# Smart_AC_Meter.net
KiCad netlist of a schematic drawn in Altium Designer
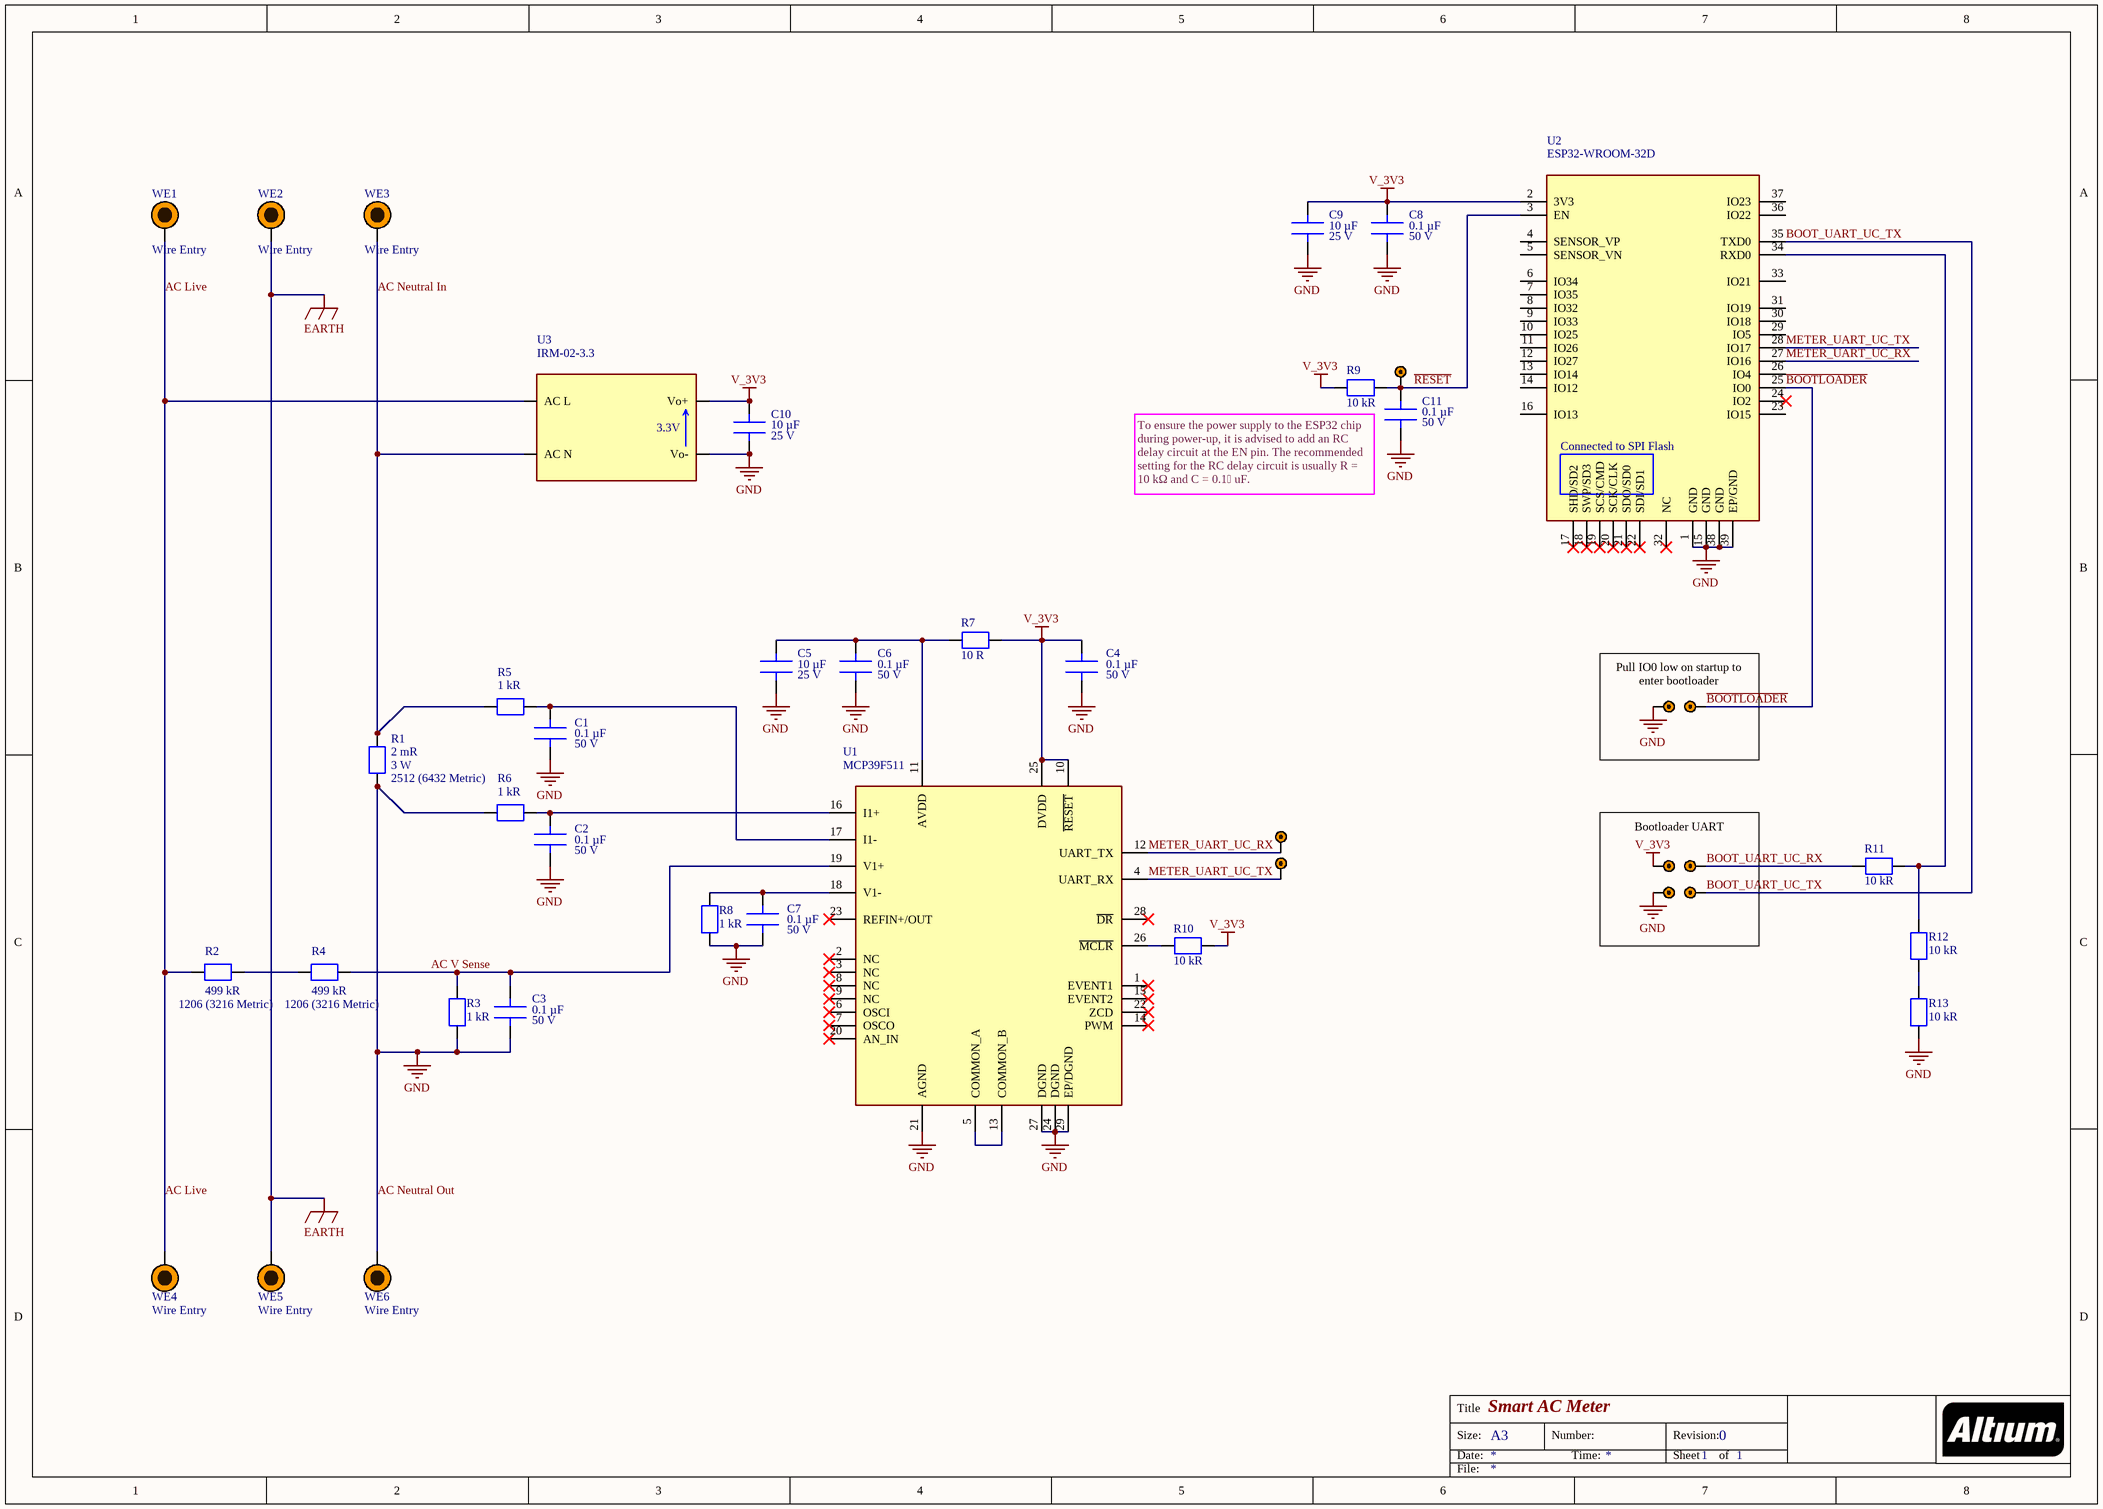
[diagram p0: Smart_AC_Meter.SchDoc]

(export (version "E")
  (design (tool "Eeschema 10.0.6"))
  (components
    (comp (ref "C1")
      (value "Capacitor")
      (footprint "0805")
      (description "AVX Corporation 08055D104KAT2A")
      (fields
        (field (name "UNIQUE PART NUMBER") "LM_CAP_0001")
        (field (name "DIGIKEY PART NUMBER") "478-12790-1-ND")
        (field (name "CAPACITANCE") "0.1 µF")
        (field (name "VOLTAGE") "50 V")
      )
      (libsource (lib "Database") (part "Capacitor"))
    )
    (comp (ref "C2")
      (value "Capacitor")
      (footprint "0805")
      (description "AVX Corporation 08055D104KAT2A")
      (fields
        (field (name "UNIQUE PART NUMBER") "LM_CAP_0001")
        (field (name "DIGIKEY PART NUMBER") "478-12790-1-ND")
        (field (name "CAPACITANCE") "0.1 µF")
        (field (name "VOLTAGE") "50 V")
      )
      (libsource (lib "Database") (part "Capacitor"))
    )
    (comp (ref "C3")
      (value "Capacitor")
      (footprint "0805")
      (description "AVX Corporation 08055D104KAT2A")
      (fields
        (field (name "CAPACITANCE") "0.1 µF")
        (field (name "UNIQUE PART NUMBER") "LM_CAP_0001")
        (field (name "DIGIKEY PART NUMBER") "478-12790-1-ND")
        (field (name "VOLTAGE") "50 V")
      )
      (libsource (lib "Database") (part "Capacitor"))
    )
    (comp (ref "C4")
      (value "Capacitor")
      (footprint "0805")
      (description "AVX Corporation 08055D104KAT2A")
      (fields
        (field (name "UNIQUE PART NUMBER") "LM_CAP_0001")
        (field (name "DIGIKEY PART NUMBER") "478-12790-1-ND")
        (field (name "CAPACITANCE") "0.1 µF")
        (field (name "VOLTAGE") "50 V")
      )
      (libsource (lib "Database") (part "Capacitor"))
    )
    (comp (ref "C5")
      (value "Capacitor")
      (footprint "0805")
      (fields
        (field (name "CAPACITANCE") "10 µF")
        (field (name "UNIQUE PART NUMBER") "LM_CAP_0002")
        (field (name "MANUFACTURER PART NUMBER") "Taiyo Yuden TMK212BBJ106KG-T")
        (field (name "DIGIKEY PART NUMBER") "587-2985-1-ND")
        (field (name "VOLTAGE") "25 V")
      )
      (libsource (lib "Database") (part "Capacitor"))
    )
    (comp (ref "C6")
      (value "Capacitor")
      (footprint "0805")
      (description "AVX Corporation 08055D104KAT2A")
      (fields
        (field (name "UNIQUE PART NUMBER") "LM_CAP_0001")
        (field (name "DIGIKEY PART NUMBER") "478-12790-1-ND")
        (field (name "CAPACITANCE") "0.1 µF")
        (field (name "VOLTAGE") "50 V")
      )
      (libsource (lib "Database") (part "Capacitor"))
    )
    (comp (ref "C7")
      (value "Capacitor")
      (footprint "0805")
      (description "AVX Corporation 08055D104KAT2A")
      (fields
        (field (name "CAPACITANCE") "0.1 µF")
        (field (name "UNIQUE PART NUMBER") "LM_CAP_0001")
        (field (name "DIGIKEY PART NUMBER") "478-12790-1-ND")
        (field (name "VOLTAGE") "50 V")
      )
      (libsource (lib "Database") (part "Capacitor"))
    )
    (comp (ref "C8")
      (value "Capacitor")
      (footprint "0805")
      (description "AVX Corporation 08055D104KAT2A")
      (fields
        (field (name "UNIQUE PART NUMBER") "LM_CAP_0001")
        (field (name "DIGIKEY PART NUMBER") "478-12790-1-ND")
        (field (name "CAPACITANCE") "0.1 µF")
        (field (name "VOLTAGE") "50 V")
      )
      (libsource (lib "Database") (part "Capacitor"))
    )
    (comp (ref "C9")
      (value "Capacitor")
      (footprint "0805")
      (fields
        (field (name "CAPACITANCE") "10 µF")
        (field (name "UNIQUE PART NUMBER") "LM_CAP_0002")
        (field (name "MANUFACTURER PART NUMBER") "Taiyo Yuden TMK212BBJ106KG-T")
        (field (name "DIGIKEY PART NUMBER") "587-2985-1-ND")
        (field (name "VOLTAGE") "25 V")
      )
      (libsource (lib "Database") (part "Capacitor"))
    )
    (comp (ref "C10")
      (value "Capacitor")
      (footprint "0805")
      (fields
        (field (name "CAPACITANCE") "10 µF")
        (field (name "UNIQUE PART NUMBER") "LM_CAP_0002")
        (field (name "MANUFACTURER PART NUMBER") "Taiyo Yuden TMK212BBJ106KG-T")
        (field (name "DIGIKEY PART NUMBER") "587-2985-1-ND")
        (field (name "VOLTAGE") "25 V")
      )
      (libsource (lib "Database") (part "Capacitor"))
    )
    (comp (ref "C11")
      (value "Capacitor")
      (footprint "0805")
      (description "AVX Corporation 08055D104KAT2A")
      (fields
        (field (name "UNIQUE PART NUMBER") "LM_CAP_0001")
        (field (name "DIGIKEY PART NUMBER") "478-12790-1-ND")
        (field (name "CAPACITANCE") "0.1 µF")
        (field (name "VOLTAGE") "50 V")
      )
      (libsource (lib "Database") (part "Capacitor"))
    )
    (comp (ref "R1")
      (value "Resistor")
      (footprint "2512")
      (fields
        (field (name "UNIQUE PART NUMBER") "LM_RES_0002")
        (field (name "MANUFACTURER PART NUMBER") "Riedon CSRL3-0R002F8")
        (field (name "DIGIKEY PART NUMBER") "696-1836-1-ND")
        (field (name "RESISTANCE") "2 mR")
        (field (name "POWER") "3 W")
        (field (name "PACKAGE") "2512 (6432 Metric)")
      )
      (libsource (lib "Database") (part "Resistor"))
    )
    (comp (ref "R2")
      (value "Resistor")
      (footprint "1206")
      (fields
        (field (name "UNIQUE PART NUMBER") "LM_RES_0003")
        (field (name "MANUFACTURER PART NUMBER") "Stackpole Electronics Inc RMCF1206FT499K")
        (field (name "DIGIKEY PART NUMBER") "RMCF1206FT499KCT-ND")
        (field (name "RESISTANCE") "499 kR")
        (field (name "PACKAGE") "1206 (3216 Metric)")
      )
      (libsource (lib "Database") (part "Resistor"))
    )
    (comp (ref "R3")
      (value "Resistor")
      (footprint "0805")
      (fields
        (field (name "UNIQUE PART NUMBER") "LM_RES_0001")
        (field (name "MANUFACTURER PART NUMBER") "Stackpole Electronics Inc RMCF0805FT1K00")
        (field (name "DIGIKEY PART NUMBER") "RMCF0805FT1K00CT-ND")
        (field (name "RESISTANCE") "1 kR")
      )
      (libsource (lib "Database") (part "Resistor"))
    )
    (comp (ref "R4")
      (value "Resistor")
      (footprint "1206")
      (fields
        (field (name "UNIQUE PART NUMBER") "LM_RES_0003")
        (field (name "MANUFACTURER PART NUMBER") "Stackpole Electronics Inc RMCF1206FT499K")
        (field (name "DIGIKEY PART NUMBER") "RMCF1206FT499KCT-ND")
        (field (name "RESISTANCE") "499 kR")
        (field (name "PACKAGE") "1206 (3216 Metric)")
      )
      (libsource (lib "Database") (part "Resistor"))
    )
    (comp (ref "R5")
      (value "Resistor")
      (footprint "0805")
      (fields
        (field (name "UNIQUE PART NUMBER") "LM_RES_0001")
        (field (name "MANUFACTURER PART NUMBER") "Stackpole Electronics Inc RMCF0805FT1K00")
        (field (name "DIGIKEY PART NUMBER") "RMCF0805FT1K00CT-ND")
        (field (name "RESISTANCE") "1 kR")
      )
      (libsource (lib "Database") (part "Resistor"))
    )
    (comp (ref "R6")
      (value "Resistor")
      (footprint "0805")
      (fields
        (field (name "UNIQUE PART NUMBER") "LM_RES_0001")
        (field (name "MANUFACTURER PART NUMBER") "Stackpole Electronics Inc RMCF0805FT1K00")
        (field (name "DIGIKEY PART NUMBER") "RMCF0805FT1K00CT-ND")
        (field (name "RESISTANCE") "1 kR")
      )
      (libsource (lib "Database") (part "Resistor"))
    )
    (comp (ref "R7")
      (value "Resistor")
      (footprint "0805")
      (fields
        (field (name "RESISTANCE") "10 R")
        (field (name "UNIQUE PART NUMBER") "LM_RES_0004")
        (field (name "MANUFACTURER PART NUMBER") "Stackpole Electronics Inc RMCF0805FT10R0")
        (field (name "DIGIKEY PART NUMBER") "RMCF0805FT10R0CT-ND")
      )
      (libsource (lib "Database") (part "Resistor"))
    )
    (comp (ref "R8")
      (value "Resistor")
      (footprint "0805")
      (fields
        (field (name "UNIQUE PART NUMBER") "LM_RES_0001")
        (field (name "MANUFACTURER PART NUMBER") "Stackpole Electronics Inc RMCF0805FT1K00")
        (field (name "DIGIKEY PART NUMBER") "RMCF0805FT1K00CT-ND")
        (field (name "RESISTANCE") "1 kR")
      )
      (libsource (lib "Database") (part "Resistor"))
    )
    (comp (ref "R9")
      (value "Resistor")
      (footprint "0805")
      (fields
        (field (name "RESISTANCE") "10 kR")
        (field (name "UNIQUE PART NUMBER") "LM_RES_0005")
        (field (name "MANUFACTURER PART NUMBER") "Stackpole Electronics Inc RMCF0805FT10K0")
        (field (name "DIGIKEY PART NUMBER") "RMCF0805FT10K0CT-ND")
      )
      (libsource (lib "Database") (part "Resistor"))
    )
    (comp (ref "R10")
      (value "Resistor")
      (footprint "0805")
      (fields
        (field (name "RESISTANCE") "10 kR")
        (field (name "UNIQUE PART NUMBER") "LM_RES_0005")
        (field (name "MANUFACTURER PART NUMBER") "Stackpole Electronics Inc RMCF0805FT10K0")
        (field (name "DIGIKEY PART NUMBER") "RMCF0805FT10K0CT-ND")
      )
      (libsource (lib "Database") (part "Resistor"))
    )
    (comp (ref "R11")
      (value "Resistor")
      (footprint "0805")
      (fields
        (field (name "RESISTANCE") "10 kR")
        (field (name "UNIQUE PART NUMBER") "LM_RES_0005")
        (field (name "MANUFACTURER PART NUMBER") "Stackpole Electronics Inc RMCF0805FT10K0")
        (field (name "DIGIKEY PART NUMBER") "RMCF0805FT10K0CT-ND")
      )
      (libsource (lib "Database") (part "Resistor"))
    )
    (comp (ref "R12")
      (value "Resistor")
      (footprint "0805")
      (fields
        (field (name "RESISTANCE") "10 kR")
        (field (name "UNIQUE PART NUMBER") "LM_RES_0005")
        (field (name "MANUFACTURER PART NUMBER") "Stackpole Electronics Inc RMCF0805FT10K0")
        (field (name "DIGIKEY PART NUMBER") "RMCF0805FT10K0CT-ND")
      )
      (libsource (lib "Database") (part "Resistor"))
    )
    (comp (ref "R13")
      (value "Resistor")
      (footprint "0805")
      (fields
        (field (name "RESISTANCE") "10 kR")
        (field (name "UNIQUE PART NUMBER") "LM_RES_0005")
        (field (name "MANUFACTURER PART NUMBER") "Stackpole Electronics Inc RMCF0805FT10K0")
        (field (name "DIGIKEY PART NUMBER") "RMCF0805FT10K0CT-ND")
      )
      (libsource (lib "Database") (part "Resistor"))
    )
    (comp (ref "TP1")
      (value "Via")
      (footprint "1mmVia")
      (description "1mm dia via/through hole")
      (fields (field (name "UNIQUE PART NUMBER") "LM_OTH_0002"))
      (libsource (lib "Database") (part "Via"))
    )
    (comp (ref "TP2")
      (value "Via")
      (footprint "1mmVia")
      (description "1mm dia via/through hole")
      (fields (field (name "UNIQUE PART NUMBER") "LM_OTH_0002"))
      (libsource (lib "Database") (part "Via"))
    )
    (comp (ref "TP3")
      (value "Via")
      (footprint "1mmVia")
      (description "1mm dia via/through hole")
      (fields (field (name "UNIQUE PART NUMBER") "LM_OTH_0002"))
      (libsource (lib "Database") (part "Via"))
    )
    (comp (ref "TP4")
      (value "Via")
      (footprint "1mmVia")
      (description "1mm dia via/through hole")
      (fields (field (name "UNIQUE PART NUMBER") "LM_OTH_0002"))
      (libsource (lib "Database") (part "Via"))
    )
    (comp (ref "TP5")
      (value "Via")
      (footprint "1mmVia")
      (description "1mm dia via/through hole")
      (fields (field (name "UNIQUE PART NUMBER") "LM_OTH_0002"))
      (libsource (lib "Database") (part "Via"))
    )
    (comp (ref "TP6")
      (value "Via")
      (footprint "1mmVia")
      (description "1mm dia via/through hole")
      (fields (field (name "UNIQUE PART NUMBER") "LM_OTH_0002"))
      (libsource (lib "Database") (part "Via"))
    )
    (comp (ref "TP7")
      (value "Via")
      (footprint "1mmVia")
      (description "1mm dia via/through hole")
      (fields (field (name "UNIQUE PART NUMBER") "LM_OTH_0002"))
      (libsource (lib "Database") (part "Via"))
    )
    (comp (ref "TP8")
      (value "Via")
      (footprint "1mmVia")
      (description "1mm dia via/through hole")
      (fields (field (name "UNIQUE PART NUMBER") "LM_OTH_0002"))
      (libsource (lib "Database") (part "Via"))
    )
    (comp (ref "TP9")
      (value "Via")
      (footprint "1mmVia")
      (description "1mm dia via/through hole")
      (fields (field (name "UNIQUE PART NUMBER") "LM_OTH_0002"))
      (libsource (lib "Database") (part "Via"))
    )
    (comp (ref "U1")
      (value "MCP39F511")
      (footprint "MCP39F511")
      (description "Single Phase Meter IC 28-QFN (5x5)")
      (fields
        (field (name "UNIQUE PART NUMBER") "LM_IC_0001")
        (field (name "MANUFACTURER PART NUMBER") "Microchip Technology MCP39F511-E/MQ")
      )
      (libsource (lib "Database") (part "MCP39F511"))
    )
    (comp (ref "U2")
      (value "ESP32-WROOM-32D")
      (footprint "ESP32-WROOM-32D")
      (description "Bluetooth, WiFi,3 Transceiver Module")
      (fields
        (field (name "UNIQUE PART NUMBER") "LM_IC_0002")
        (field (name "MANUFACTURER PART NUMBER") "Espressif Systems ESP32-WROOM-32D")
      )
      (libsource (lib "Database") (part "ESP32-WROOM-32D"))
    )
    (comp (ref "U3")
      (value "IRM-02-3.3")
      (footprint "IRM-02-3.3")
      (description "Enclosed AC DC Converter 1 Output 3.3V 600mA")
      (fields
        (field (name "UNIQUE PART NUMBER") "LM_IC_0003")
        (field (name "MANUFACTURER PART NUMBER") "MEAN WELL USA Inc. IRM-02-3.3")
      )
      (libsource (lib "Database") (part "IRM-02-3.3"))
    )
    (comp (ref "WE1")
      (value "Wire Entry")
      (footprint "12AWGWireEntry")
      (description "12 AWG Wire Entry")
      (fields (field (name "UNIQUE PART NUMBER") "LM_OTH_0001"))
      (libsource (lib "Database") (part "Wire Entry"))
    )
    (comp (ref "WE2")
      (value "Wire Entry")
      (footprint "12AWGWireEntry")
      (description "12 AWG Wire Entry")
      (fields (field (name "UNIQUE PART NUMBER") "LM_OTH_0001"))
      (libsource (lib "Database") (part "Wire Entry"))
    )
    (comp (ref "WE3")
      (value "Wire Entry")
      (footprint "12AWGWireEntry")
      (description "12 AWG Wire Entry")
      (fields (field (name "UNIQUE PART NUMBER") "LM_OTH_0001"))
      (libsource (lib "Database") (part "Wire Entry"))
    )
    (comp (ref "WE4")
      (value "Wire Entry")
      (footprint "12AWGWireEntry")
      (description "12 AWG Wire Entry")
      (fields (field (name "UNIQUE PART NUMBER") "LM_OTH_0001"))
      (libsource (lib "Database") (part "Wire Entry"))
    )
    (comp (ref "WE5")
      (value "Wire Entry")
      (footprint "12AWGWireEntry")
      (description "12 AWG Wire Entry")
      (fields (field (name "UNIQUE PART NUMBER") "LM_OTH_0001"))
      (libsource (lib "Database") (part "Wire Entry"))
    )
    (comp (ref "WE6")
      (value "Wire Entry")
      (footprint "12AWGWireEntry")
      (description "12 AWG Wire Entry")
      (fields (field (name "UNIQUE PART NUMBER") "LM_OTH_0001"))
      (libsource (lib "Database") (part "Wire Entry"))
    )
  )
  (nets
    (net (code "1") (name "/AC Live") (class "Default")
      (node (ref "R2") (pin "1") (pinfunction "1_1") (pintype "passive"))
      (node (ref "U3") (pin "1") (pinfunction "AC_L_1") (pintype "passive"))
      (node (ref "WE1") (pin "1") (pinfunction "1_1") (pintype "passive"))
      (node (ref "WE4") (pin "1") (pinfunction "1_1") (pintype "passive"))
    )
    (net (code "2") (name "/AC Neutral In") (class "Default")
      (node (ref "R1") (pin "1") (pinfunction "1_1") (pintype "passive"))
      (node (ref "R5") (pin "1") (pinfunction "1_1") (pintype "passive"))
      (node (ref "U3") (pin "24") (pinfunction "AC_N_24") (pintype "passive"))
      (node (ref "WE3") (pin "1") (pinfunction "1_1") (pintype "passive"))
    )
    (net (code "3") (name "/AC V Sense") (class "Default")
      (node (ref "C3") (pin "1") (pinfunction "1_1") (pintype "passive"))
      (node (ref "R3") (pin "1") (pinfunction "1_1") (pintype "passive"))
      (node (ref "R4") (pin "2") (pinfunction "2_2") (pintype "passive"))
      (node (ref "U1") (pin "19") (pinfunction "V1+_19") (pintype "passive"))
    )
    (net (code "4") (name "/BOOT_UART_UC_RX") (class "Default")
      (node (ref "R11") (pin "1") (pinfunction "1_1") (pintype "passive"))
      (node (ref "TP4") (pin "1") (pinfunction "1_1") (pintype "passive"))
    )
    (net (code "5") (name "/BOOT_UART_UC_TX") (class "Default")
      (node (ref "TP6") (pin "1") (pinfunction "1_1") (pintype "passive"))
      (node (ref "U2") (pin "35") (pinfunction "TXD0_35") (pintype "passive"))
    )
    (net (code "6") (name "/METER_UART_UC_RX") (class "Default")
      (node (ref "TP7") (pin "1") (pinfunction "1_1") (pintype "passive"))
      (node (ref "U1") (pin "12") (pinfunction "UART_TX_12") (pintype "passive"))
      (node (ref "U2") (pin "27") (pinfunction "IO16_27") (pintype "passive"))
    )
    (net (code "7") (name "/METER_UART_UC_TX") (class "Default")
      (node (ref "TP8") (pin "1") (pinfunction "1_1") (pintype "passive"))
      (node (ref "U1") (pin "4") (pinfunction "UART_RX_4") (pintype "passive"))
      (node (ref "U2") (pin "28") (pinfunction "IO17_28") (pintype "passive"))
    )
    (net (code "8") (name "/~{BOOTLOADER}") (class "Default")
      (node (ref "TP2") (pin "1") (pinfunction "1_1") (pintype "passive"))
      (node (ref "U2") (pin "25") (pinfunction "IO0_25") (pintype "passive"))
    )
    (net (code "9") (name "/~{RESET}") (class "Default")
      (node (ref "C11") (pin "1") (pinfunction "1_1") (pintype "passive"))
      (node (ref "R9") (pin "2") (pinfunction "2_2") (pintype "passive"))
      (node (ref "TP9") (pin "1") (pinfunction "1_1") (pintype "passive"))
      (node (ref "U2") (pin "3") (pinfunction "EN_3") (pintype "passive"))
    )
    (net (code "10") (name "EARTH") (class "Default")
      (node (ref "WE2") (pin "1") (pinfunction "1_1") (pintype "passive"))
      (node (ref "WE5") (pin "1") (pinfunction "1_1") (pintype "passive"))
    )
    (net (code "11") (name "GND") (class "Default")
      (node (ref "C1") (pin "2") (pinfunction "2_2") (pintype "passive"))
      (node (ref "C10") (pin "1") (pinfunction "1_1") (pintype "passive"))
      (node (ref "C11") (pin "2") (pinfunction "2_2") (pintype "passive"))
      (node (ref "C2") (pin "2") (pinfunction "2_2") (pintype "passive"))
      (node (ref "C3") (pin "2") (pinfunction "2_2") (pintype "passive"))
      (node (ref "C4") (pin "2") (pinfunction "2_2") (pintype "passive"))
      (node (ref "C5") (pin "2") (pinfunction "2_2") (pintype "passive"))
      (node (ref "C6") (pin "2") (pinfunction "2_2") (pintype "passive"))
      (node (ref "C7") (pin "2") (pinfunction "2_2") (pintype "passive"))
      (node (ref "C8") (pin "2") (pinfunction "2_2") (pintype "passive"))
      (node (ref "C9") (pin "1") (pinfunction "1_1") (pintype "passive"))
      (node (ref "R1") (pin "2") (pinfunction "2_2") (pintype "passive"))
      (node (ref "R13") (pin "1") (pinfunction "1_1") (pintype "passive"))
      (node (ref "R3") (pin "2") (pinfunction "2_2") (pintype "passive"))
      (node (ref "R6") (pin "1") (pinfunction "1_1") (pintype "passive"))
      (node (ref "R8") (pin "1") (pinfunction "1_1") (pintype "passive"))
      (node (ref "TP1") (pin "1") (pinfunction "1_1") (pintype "passive"))
      (node (ref "TP5") (pin "1") (pinfunction "1_1") (pintype "passive"))
      (node (ref "U1") (pin "21") (pinfunction "AGND_21") (pintype "passive"))
      (node (ref "U1") (pin "24") (pinfunction "DGND_24") (pintype "passive"))
      (node (ref "U1") (pin "27") (pinfunction "DGND_27") (pintype "passive"))
      (node (ref "U1") (pin "29") (pinfunction "EP/DGND_29") (pintype "passive"))
      (node (ref "U2") (pin "1") (pinfunction "GND_1") (pintype "passive"))
      (node (ref "U2") (pin "15") (pinfunction "GND_15") (pintype "passive"))
      (node (ref "U2") (pin "38") (pinfunction "GND_38") (pintype "passive"))
      (node (ref "U2") (pin "39") (pinfunction "EP/GND_39") (pintype "passive"))
      (node (ref "U3") (pin "13") (pinfunction "Vo-_13") (pintype "passive"))
      (node (ref "WE6") (pin "1") (pinfunction "1_1") (pintype "passive"))
    )
    (net (code "12") (name "Net-(R2-Pad2)") (class "Default")
      (node (ref "R2") (pin "2") (pinfunction "2_2") (pintype "passive"))
      (node (ref "R4") (pin "1") (pinfunction "1_1") (pintype "passive"))
    )
    (net (code "13") (name "Net-(R12-Pad1)") (class "Default")
      (node (ref "R12") (pin "1") (pinfunction "1_1") (pintype "passive"))
      (node (ref "R13") (pin "2") (pinfunction "2_2") (pintype "passive"))
    )
    (net (code "14") (name "Net-(U1-AVDD)") (class "Default")
      (node (ref "C5") (pin "1") (pinfunction "1_1") (pintype "passive"))
      (node (ref "C6") (pin "1") (pinfunction "1_1") (pintype "passive"))
      (node (ref "R7") (pin "1") (pinfunction "1_1") (pintype "passive"))
      (node (ref "U1") (pin "11") (pinfunction "AVDD_11") (pintype "passive"))
    )
    (net (code "15") (name "Net-(U1-COMMON_A)") (class "Default")
      (node (ref "U1") (pin "13") (pinfunction "COMMON_B_13") (pintype "passive"))
      (node (ref "U1") (pin "5") (pinfunction "COMMON_A_5") (pintype "passive"))
    )
    (net (code "16") (name "Net-(U1-I1+)") (class "Default")
      (node (ref "C2") (pin "1") (pinfunction "1_1") (pintype "passive"))
      (node (ref "R6") (pin "2") (pinfunction "2_2") (pintype "passive"))
      (node (ref "U1") (pin "16") (pinfunction "I1+_16") (pintype "passive"))
    )
    (net (code "17") (name "Net-(U1-I1-)") (class "Default")
      (node (ref "C1") (pin "1") (pinfunction "1_1") (pintype "passive"))
      (node (ref "R5") (pin "2") (pinfunction "2_2") (pintype "passive"))
      (node (ref "U1") (pin "17") (pinfunction "I1-_17") (pintype "passive"))
    )
    (net (code "18") (name "Net-(U1-V1-)") (class "Default")
      (node (ref "C7") (pin "1") (pinfunction "1_1") (pintype "passive"))
      (node (ref "R8") (pin "2") (pinfunction "2_2") (pintype "passive"))
      (node (ref "U1") (pin "18") (pinfunction "V1-_18") (pintype "passive"))
    )
    (net (code "19") (name "Net-(U1-~{MCLR})") (class "Default")
      (node (ref "R10") (pin "1") (pinfunction "1_1") (pintype "passive"))
      (node (ref "U1") (pin "26") (pinfunction "~{MCLR}_26") (pintype "passive"))
    )
    (net (code "20") (name "Net-(U2-RXD0)") (class "Default")
      (node (ref "R11") (pin "2") (pinfunction "2_2") (pintype "passive"))
      (node (ref "R12") (pin "2") (pinfunction "2_2") (pintype "passive"))
      (node (ref "U2") (pin "34") (pinfunction "RXD0_34") (pintype "passive"))
    )
    (net (code "21") (name "V_3V3") (class "Default")
      (node (ref "C10") (pin "2") (pinfunction "2_2") (pintype "passive"))
      (node (ref "C4") (pin "1") (pinfunction "1_1") (pintype "passive"))
      (node (ref "C8") (pin "1") (pinfunction "1_1") (pintype "passive"))
      (node (ref "C9") (pin "2") (pinfunction "2_2") (pintype "passive"))
      (node (ref "R10") (pin "2") (pinfunction "2_2") (pintype "passive"))
      (node (ref "R7") (pin "2") (pinfunction "2_2") (pintype "passive"))
      (node (ref "R9") (pin "1") (pinfunction "1_1") (pintype "passive"))
      (node (ref "TP3") (pin "1") (pinfunction "1_1") (pintype "passive"))
      (node (ref "U1") (pin "10") (pinfunction "~{RESET}_10") (pintype "passive"))
      (node (ref "U1") (pin "25") (pinfunction "DVDD_25") (pintype "passive"))
      (node (ref "U2") (pin "2") (pinfunction "3V3_2") (pintype "passive"))
      (node (ref "U3") (pin "12") (pinfunction "Vo+_12") (pintype "passive"))
    )
    (net (code "22") (name "unconnected-(U1-AN_IN-Pad20)") (class "Default")
      (node (ref "U1") (pin "20") (pinfunction "AN_IN_20") (pintype "passive+no_connect"))
    )
    (net (code "23") (name "unconnected-(U1-EVENT1-Pad1)") (class "Default")
      (node (ref "U1") (pin "1") (pinfunction "EVENT1_1") (pintype "passive+no_connect"))
    )
    (net (code "24") (name "unconnected-(U1-EVENT2-Pad15)") (class "Default")
      (node (ref "U1") (pin "15") (pinfunction "EVENT2_15") (pintype "passive+no_connect"))
    )
    (net (code "25") (name "unconnected-(U1-NC-Pad2)") (class "Default")
      (node (ref "U1") (pin "2") (pinfunction "NC_2") (pintype "passive+no_connect"))
    )
    (net (code "26") (name "unconnected-(U1-NC-Pad3)") (class "Default")
      (node (ref "U1") (pin "3") (pinfunction "NC_3") (pintype "passive+no_connect"))
    )
    (net (code "27") (name "unconnected-(U1-NC-Pad8)") (class "Default")
      (node (ref "U1") (pin "8") (pinfunction "NC_8") (pintype "passive+no_connect"))
    )
    (net (code "28") (name "unconnected-(U1-NC-Pad9)") (class "Default")
      (node (ref "U1") (pin "9") (pinfunction "NC_9") (pintype "passive+no_connect"))
    )
    (net (code "29") (name "unconnected-(U1-OSCI-Pad6)") (class "Default")
      (node (ref "U1") (pin "6") (pinfunction "OSCI_6") (pintype "passive+no_connect"))
    )
    (net (code "30") (name "unconnected-(U1-OSCO-Pad7)") (class "Default")
      (node (ref "U1") (pin "7") (pinfunction "OSCO_7") (pintype "passive+no_connect"))
    )
    (net (code "31") (name "unconnected-(U1-PWM-Pad14)") (class "Default")
      (node (ref "U1") (pin "14") (pinfunction "PWM_14") (pintype "passive+no_connect"))
    )
    (net (code "32") (name "unconnected-(U1-REFIN+{slash}OUT-Pad23)") (class "Default")
      (node (ref "U1") (pin "23") (pinfunction "REFIN+/OUT_23") (pintype "passive+no_connect"))
    )
    (net (code "33") (name "unconnected-(U1-ZCD-Pad22)") (class "Default")
      (node (ref "U1") (pin "22") (pinfunction "ZCD_22") (pintype "passive+no_connect"))
    )
    (net (code "34") (name "unconnected-(U1-~{DR}-Pad28)") (class "Default")
      (node (ref "U1") (pin "28") (pinfunction "~{DR}_28") (pintype "passive+no_connect"))
    )
    (net (code "35") (name "unconnected-(U2-IO2-Pad24)") (class "Default")
      (node (ref "U2") (pin "24") (pinfunction "IO2_24") (pintype "passive+no_connect"))
    )
    (net (code "36") (name "unconnected-(U2-IO4-Pad26)") (class "Default")
      (node (ref "U2") (pin "26") (pinfunction "IO4_26") (pintype "passive"))
    )
    (net (code "37") (name "unconnected-(U2-IO5-Pad29)") (class "Default")
      (node (ref "U2") (pin "29") (pinfunction "IO5_29") (pintype "passive"))
    )
    (net (code "38") (name "unconnected-(U2-IO12-Pad14)") (class "Default")
      (node (ref "U2") (pin "14") (pinfunction "IO12_14") (pintype "passive"))
    )
    (net (code "39") (name "unconnected-(U2-IO13-Pad16)") (class "Default")
      (node (ref "U2") (pin "16") (pinfunction "IO13_16") (pintype "passive"))
    )
    (net (code "40") (name "unconnected-(U2-IO14-Pad13)") (class "Default")
      (node (ref "U2") (pin "13") (pinfunction "IO14_13") (pintype "passive"))
    )
    (net (code "41") (name "unconnected-(U2-IO15-Pad23)") (class "Default")
      (node (ref "U2") (pin "23") (pinfunction "IO15_23") (pintype "passive"))
    )
    (net (code "42") (name "unconnected-(U2-IO18-Pad30)") (class "Default")
      (node (ref "U2") (pin "30") (pinfunction "IO18_30") (pintype "passive"))
    )
    (net (code "43") (name "unconnected-(U2-IO19-Pad31)") (class "Default")
      (node (ref "U2") (pin "31") (pinfunction "IO19_31") (pintype "passive"))
    )
    (net (code "44") (name "unconnected-(U2-IO21-Pad33)") (class "Default")
      (node (ref "U2") (pin "33") (pinfunction "IO21_33") (pintype "passive"))
    )
    (net (code "45") (name "unconnected-(U2-IO22-Pad36)") (class "Default")
      (node (ref "U2") (pin "36") (pinfunction "IO22_36") (pintype "passive"))
    )
    (net (code "46") (name "unconnected-(U2-IO23-Pad37)") (class "Default")
      (node (ref "U2") (pin "37") (pinfunction "IO23_37") (pintype "passive"))
    )
    (net (code "47") (name "unconnected-(U2-IO25-Pad10)") (class "Default")
      (node (ref "U2") (pin "10") (pinfunction "IO25_10") (pintype "passive"))
    )
    (net (code "48") (name "unconnected-(U2-IO26-Pad11)") (class "Default")
      (node (ref "U2") (pin "11") (pinfunction "IO26_11") (pintype "passive"))
    )
    (net (code "49") (name "unconnected-(U2-IO27-Pad12)") (class "Default")
      (node (ref "U2") (pin "12") (pinfunction "IO27_12") (pintype "passive"))
    )
    (net (code "50") (name "unconnected-(U2-IO32-Pad8)") (class "Default")
      (node (ref "U2") (pin "8") (pinfunction "IO32_8") (pintype "passive"))
    )
    (net (code "51") (name "unconnected-(U2-IO33-Pad9)") (class "Default")
      (node (ref "U2") (pin "9") (pinfunction "IO33_9") (pintype "passive"))
    )
    (net (code "52") (name "unconnected-(U2-IO34-Pad6)") (class "Default")
      (node (ref "U2") (pin "6") (pinfunction "IO34_6") (pintype "passive"))
    )
    (net (code "53") (name "unconnected-(U2-IO35-Pad7)") (class "Default")
      (node (ref "U2") (pin "7") (pinfunction "IO35_7") (pintype "passive"))
    )
    (net (code "54") (name "unconnected-(U2-NC-Pad32)") (class "Default")
      (node (ref "U2") (pin "32") (pinfunction "NC_32") (pintype "passive+no_connect"))
    )
    (net (code "55") (name "unconnected-(U2-SCK{slash}CLK-Pad20)") (class "Default")
      (node (ref "U2") (pin "20") (pinfunction "SCK/CLK_20") (pintype "passive+no_connect"))
    )
    (net (code "56") (name "unconnected-(U2-SCS{slash}CMD-Pad19)") (class "Default")
      (node (ref "U2") (pin "19") (pinfunction "SCS/CMD_19") (pintype "passive+no_connect"))
    )
    (net (code "57") (name "unconnected-(U2-SDI{slash}SD1-Pad22)") (class "Default")
      (node (ref "U2") (pin "22") (pinfunction "SDI/SD1_22") (pintype "passive+no_connect"))
    )
    (net (code "58") (name "unconnected-(U2-SDO{slash}SD0-Pad21)") (class "Default")
      (node (ref "U2") (pin "21") (pinfunction "SDO/SD0_21") (pintype "passive+no_connect"))
    )
    (net (code "59") (name "unconnected-(U2-SENSOR_VN-Pad5)") (class "Default")
      (node (ref "U2") (pin "5") (pinfunction "SENSOR_VN_5") (pintype "passive"))
    )
    (net (code "60") (name "unconnected-(U2-SENSOR_VP-Pad4)") (class "Default")
      (node (ref "U2") (pin "4") (pinfunction "SENSOR_VP_4") (pintype "passive"))
    )
    (net (code "61") (name "unconnected-(U2-SHD{slash}SD2-Pad17)") (class "Default")
      (node (ref "U2") (pin "17") (pinfunction "SHD/SD2_17") (pintype "passive+no_connect"))
    )
    (net (code "62") (name "unconnected-(U2-SWP{slash}SD3-Pad18)") (class "Default")
      (node (ref "U2") (pin "18") (pinfunction "SWP/SD3_18") (pintype "passive+no_connect"))
    )
  )
)
